# Sheet1.net
KiCad netlist of a schematic drawn in Altium Designer
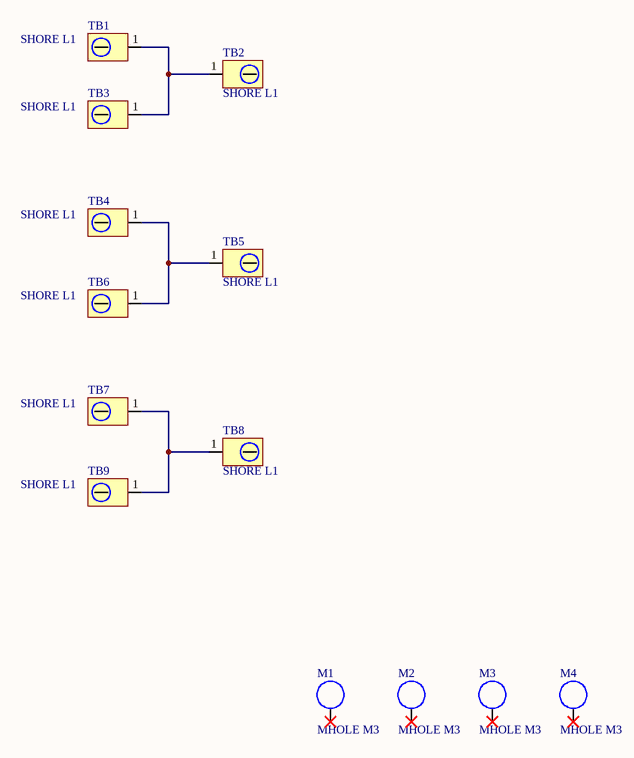
[diagram p0: Sheet1.SchDoc]

(export (version "E")
  (design (tool "Eeschema 10.0.6"))
  (components
    (comp (ref "M1") (value "MHOLE M3") (footprint "MHOLE_M3") (libsource (lib "IdaTech") (part "MHOLE M3")))
    (comp (ref "M2") (value "MHOLE M3") (footprint "MHOLE_M3") (libsource (lib "IdaTech") (part "MHOLE M3")))
    (comp (ref "M3") (value "MHOLE M3") (footprint "MHOLE_M3") (libsource (lib "IdaTech") (part "MHOLE M3")))
    (comp (ref "M4") (value "MHOLE M3") (footprint "MHOLE_M3") (libsource (lib "IdaTech") (part "MHOLE M3")))
    (comp (ref "TB1")
      (value "SHORE L1")
      (footprint "B6A-PCB-XX")
      (libsource (lib "") (part "ScrewLug_6awg_1"))
    )
    (comp (ref "TB2")
      (value "SHORE L1")
      (footprint "B6A-PCB-XX")
      (libsource (lib "Sch Symbols") (part "ScrewLug_6awg"))
    )
    (comp (ref "TB3")
      (value "SHORE L1")
      (footprint "B6A-PCB-XX")
      (libsource (lib "") (part "ScrewLug_6awg_1"))
    )
    (comp (ref "TB4")
      (value "SHORE L1")
      (footprint "B6A-PCB-XX")
      (libsource (lib "") (part "ScrewLug_6awg_1"))
    )
    (comp (ref "TB5")
      (value "SHORE L1")
      (footprint "B6A-PCB-XX")
      (libsource (lib "Sch Symbols") (part "ScrewLug_6awg"))
    )
    (comp (ref "TB6")
      (value "SHORE L1")
      (footprint "B6A-PCB-XX")
      (libsource (lib "") (part "ScrewLug_6awg_1"))
    )
    (comp (ref "TB7")
      (value "SHORE L1")
      (footprint "B6A-PCB-XX")
      (libsource (lib "") (part "ScrewLug_6awg_1"))
    )
    (comp (ref "TB8")
      (value "SHORE L1")
      (footprint "B6A-PCB-XX")
      (libsource (lib "Sch Symbols") (part "ScrewLug_6awg"))
    )
    (comp (ref "TB9")
      (value "SHORE L1")
      (footprint "B6A-PCB-XX")
      (libsource (lib "") (part "ScrewLug_6awg_1"))
    )
  )
  (nets
    (net (code "1") (name "Net-(TB1-Pad1)") (class "Default")
      (node (ref "TB1") (pin "1") (pinfunction "1_1") (pintype "passive"))
      (node (ref "TB2") (pin "1") (pinfunction "1_1") (pintype "passive"))
      (node (ref "TB3") (pin "1") (pinfunction "1_1") (pintype "passive"))
    )
    (net (code "2") (name "Net-(TB4-Pad1)") (class "Default")
      (node (ref "TB4") (pin "1") (pinfunction "1_1") (pintype "passive"))
      (node (ref "TB5") (pin "1") (pinfunction "1_1") (pintype "passive"))
      (node (ref "TB6") (pin "1") (pinfunction "1_1") (pintype "passive"))
    )
    (net (code "3") (name "Net-(TB7-Pad1)") (class "Default")
      (node (ref "TB7") (pin "1") (pinfunction "1_1") (pintype "passive"))
      (node (ref "TB8") (pin "1") (pinfunction "1_1") (pintype "passive"))
      (node (ref "TB9") (pin "1") (pinfunction "1_1") (pintype "passive"))
    )
    (net (code "4") (name "unconnected-(M1-Pad1)") (class "Default")
      (node (ref "M1") (pin "1") (pinfunction "1_1") (pintype "passive+no_connect"))
    )
    (net (code "5") (name "unconnected-(M2-Pad1)") (class "Default")
      (node (ref "M2") (pin "1") (pinfunction "1_1") (pintype "passive+no_connect"))
    )
    (net (code "6") (name "unconnected-(M3-Pad1)") (class "Default")
      (node (ref "M3") (pin "1") (pinfunction "1_1") (pintype "passive+no_connect"))
    )
    (net (code "7") (name "unconnected-(M4-Pad1)") (class "Default")
      (node (ref "M4") (pin "1") (pinfunction "1_1") (pintype "passive+no_connect"))
    )
  )
)
